# Keg_Cop_-_Meter_Breakout.net
KiCad netlist of a schematic drawn in EAGLE
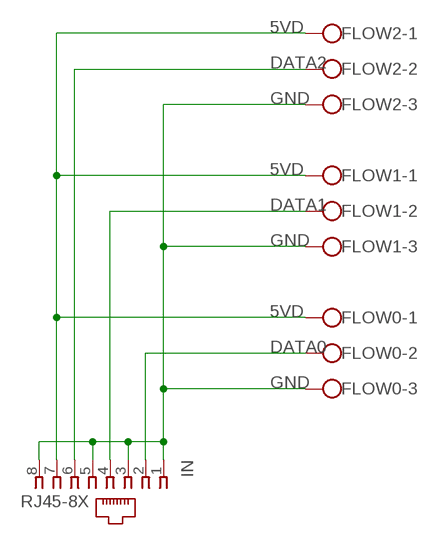
[diagram p0: schematic, sheet 1]

(export (version "E")
  (design (tool "Eeschema 10.0.6"))
  (components
    (comp (ref "FLOW0")
      (value "W237-103")
      (footprint "eagle-import:W237-103")
      (fields (field (name "MPN") "237-103"))
      (libsource (lib "eagle-import") (part "W237-103"))
    )
    (comp (ref "FLOW1")
      (value "W237-103")
      (footprint "eagle-import:W237-103")
      (fields (field (name "MPN") "237-103"))
      (libsource (lib "eagle-import") (part "W237-103"))
    )
    (comp (ref "FLOW2")
      (value "W237-103")
      (footprint "eagle-import:W237-103")
      (fields (field (name "MPN") "237-103"))
      (libsource (lib "eagle-import") (part "W237-103"))
    )
    (comp (ref "IN")
      (value "RJ45-8X")
      (footprint "eagle-import:RJ45-NO-SHIELD")
      (libsource (lib "eagle-import") (part "RJ45-8X"))
    )
  )
  (nets
    (net (code "1") (name "/5VD") (class "Default")
      (node (ref "FLOW0") (pin "1") (pinfunction "KL_1") (pintype "passive"))
      (node (ref "FLOW1") (pin "1") (pinfunction "KL_1") (pintype "passive"))
      (node (ref "FLOW2") (pin "1") (pinfunction "KL_1") (pintype "passive"))
      (node (ref "IN") (pin "7") (pinfunction "7_7") (pintype "passive"))
    )
    (net (code "2") (name "/DATA0") (class "Default")
      (node (ref "FLOW0") (pin "2") (pinfunction "KL_2") (pintype "passive"))
      (node (ref "IN") (pin "2") (pinfunction "2_2") (pintype "passive"))
    )
    (net (code "3") (name "/DATA1") (class "Default")
      (node (ref "FLOW1") (pin "2") (pinfunction "KL_2") (pintype "passive"))
      (node (ref "IN") (pin "4") (pinfunction "4_4") (pintype "passive"))
    )
    (net (code "4") (name "/DATA2") (class "Default")
      (node (ref "FLOW2") (pin "2") (pinfunction "KL_2") (pintype "passive"))
      (node (ref "IN") (pin "6") (pinfunction "6_6") (pintype "passive"))
    )
    (net (code "5") (name "/GND") (class "Default")
      (node (ref "FLOW0") (pin "3") (pinfunction "KL_3") (pintype "passive"))
      (node (ref "FLOW1") (pin "3") (pinfunction "KL_3") (pintype "passive"))
      (node (ref "FLOW2") (pin "3") (pinfunction "KL_3") (pintype "passive"))
      (node (ref "IN") (pin "1") (pinfunction "1_1") (pintype "passive"))
      (node (ref "IN") (pin "3") (pinfunction "3_3") (pintype "passive"))
      (node (ref "IN") (pin "5") (pinfunction "5_5") (pintype "passive"))
      (node (ref "IN") (pin "8") (pinfunction "8_8") (pintype "passive"))
    )
  )
)
